# PRUC-Voltmeter_USB-Protection.net
KiCad netlist of a schematic drawn in Altium Designer
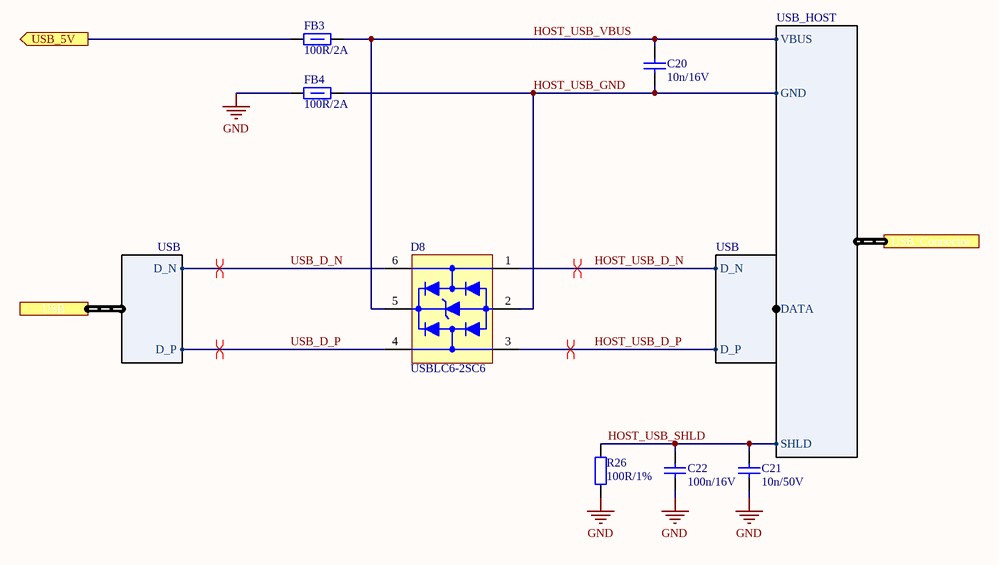
[diagram p0: PRUC-Voltmeter_USB-Protection.SchDoc]

(export (version "E")
  (design (tool "Eeschema 10.0.6"))
  (components
    (comp (ref "C20")
      (value "10n/16V")
      (footprint "MLCC_0603")
      (fields (field (name "PART NUMBER") "CL10B103KB8NNNC") (field (name "MANUFACTURER") "Samsung"))
      (libsource (lib "private") (part "Cap"))
    )
    (comp (ref "C21")
      (value "10n/50V")
      (footprint "MLCC_0805")
      (fields (field (name "PART NUMBER") "CL21B103KBANNNC") (field (name "MANUFACTURER") "Samsung"))
      (libsource (lib "private") (part "Cap"))
    )
    (comp (ref "C22")
      (value "100n/16V")
      (footprint "MLCC_0603")
      (fields (field (name "PART NUMBER") "CL10B104KO8NNNC") (field (name "MANUFACTURER") "Samsung"))
      (libsource (lib "private") (part "Cap"))
    )
    (comp (ref "D8")
      (value "USBLC6-2SC6")
      (footprint "SOT23-6")
      (fields (field (name "MANUFACTURER") "STMicroelectronics"))
      (libsource (lib "private") (part "TVS_PAPPKP"))
    )
    (comp (ref "FB3")
      (value "100R/2A")
      (footprint "FerriteBead_0603")
      (fields (field (name "PART NUMBER") "BLM18EG101TN1D") (field (name "MANUFACTURER") "Murata"))
      (libsource (lib "private") (part "FerriteBead"))
    )
    (comp (ref "FB4")
      (value "100R/2A")
      (footprint "FerriteBead_0603")
      (fields (field (name "PART NUMBER") "BLM18EG101TN1D") (field (name "MANUFACTURER") "Murata"))
      (libsource (lib "private") (part "FerriteBead"))
    )
    (comp (ref "R26")
      (value "100R/1%")
      (footprint "R_0603")
      (fields (field (name "PART NUMBER") "0603SAF1000T5E") (field (name "MANUFACTURER") "Royalohm"))
      (libsource (lib "private") (part "Res"))
    )
  )
  (nets
    (net (code "3") (name "/HOST_USB_D_N") (class "Default")
      (node (ref "D8") (pin "1") (pinfunction "I/O_1_1") (pintype "passive"))
    )
    (net (code "4") (name "/HOST_USB_D_P") (class "Default")
      (node (ref "D8") (pin "3") (pinfunction "I/O_2_3") (pintype "passive"))
    )
    (net (code "5") (name "/HOST_USB_GND") (class "Default")
      (node (ref "C20") (pin "2") (pinfunction "2_2") (pintype "passive"))
      (node (ref "D8") (pin "2") (pinfunction "GND_2") (pintype "passive"))
      (node (ref "FB4") (pin "2") (pinfunction "2_2") (pintype "passive"))
    )
    (net (code "6") (name "/HOST_USB_SHLD") (class "Default")
      (node (ref "C21") (pin "1") (pinfunction "1_1") (pintype "passive"))
      (node (ref "C22") (pin "1") (pinfunction "1_1") (pintype "passive"))
      (node (ref "R26") (pin "1") (pinfunction "1_1") (pintype "passive"))
    )
    (net (code "7") (name "/HOST_USB_VBUS") (class "Default")
      (node (ref "C20") (pin "1") (pinfunction "1_1") (pintype "passive"))
      (node (ref "D8") (pin "5") (pinfunction "VBUS_5") (pintype "passive"))
      (node (ref "FB3") (pin "2") (pinfunction "2_2") (pintype "passive"))
    )
    (net (code "8") (name "/USB_5V") (class "Default")
      (node (ref "FB3") (pin "1") (pinfunction "1_1") (pintype "passive"))
    )
    (net (code "9") (name "/USB_D_N") (class "Default")
      (node (ref "D8") (pin "6") (pinfunction "I/O_4_6") (pintype "passive"))
    )
    (net (code "10") (name "/USB_D_P") (class "Default")
      (node (ref "D8") (pin "4") (pinfunction "I/O_3_4") (pintype "passive"))
    )
    (net (code "13") (name "GND") (class "Default")
      (node (ref "C21") (pin "2") (pinfunction "2_2") (pintype "passive"))
      (node (ref "C22") (pin "2") (pinfunction "2_2") (pintype "passive"))
      (node (ref "FB4") (pin "1") (pinfunction "1_1") (pintype "passive"))
      (node (ref "R26") (pin "2") (pinfunction "2_2") (pintype "passive"))
    )
  )
)
